# moja-col2.net
KiCad netlist of a schematic drawn in EAGLE
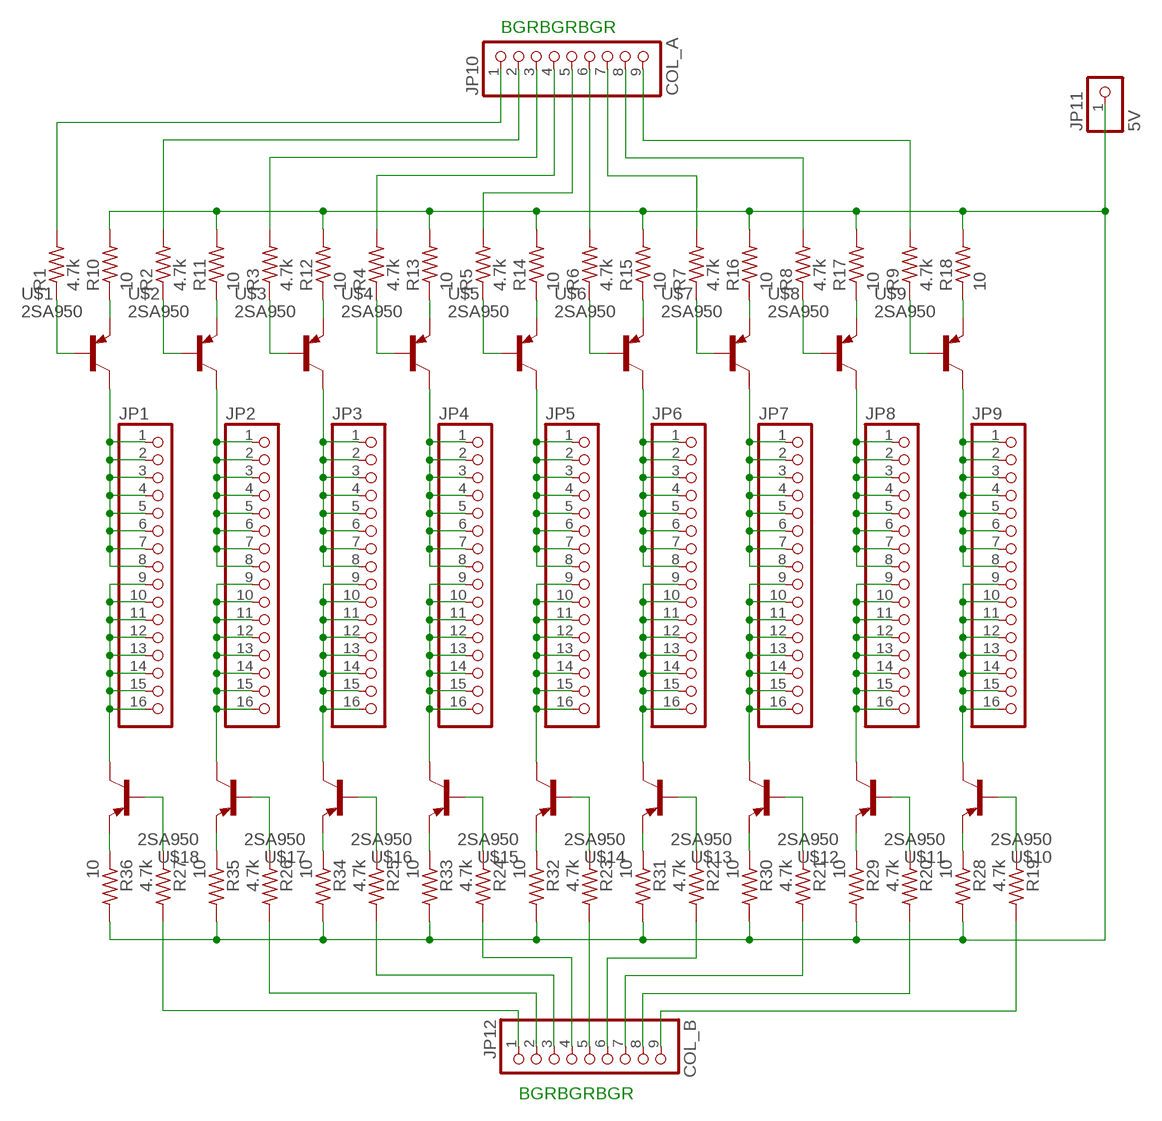
[diagram p0: schematic, sheet 1]

(export (version "E")
  (design (tool "Eeschema 10.0.6"))
  (components
    (comp (ref "JP1")
      (value "PINHD-1X16")
      (footprint "eagle-import:1X16")
      (libsource (lib "eagle-import") (part "PINHD-1X16"))
    )
    (comp (ref "JP2")
      (value "PINHD-1X16")
      (footprint "eagle-import:1X16")
      (libsource (lib "eagle-import") (part "PINHD-1X16"))
    )
    (comp (ref "JP3")
      (value "PINHD-1X16")
      (footprint "eagle-import:1X16")
      (libsource (lib "eagle-import") (part "PINHD-1X16"))
    )
    (comp (ref "JP4")
      (value "PINHD-1X16")
      (footprint "eagle-import:1X16")
      (libsource (lib "eagle-import") (part "PINHD-1X16"))
    )
    (comp (ref "JP5")
      (value "PINHD-1X16")
      (footprint "eagle-import:1X16")
      (libsource (lib "eagle-import") (part "PINHD-1X16"))
    )
    (comp (ref "JP6")
      (value "PINHD-1X16")
      (footprint "eagle-import:1X16")
      (libsource (lib "eagle-import") (part "PINHD-1X16"))
    )
    (comp (ref "JP7")
      (value "PINHD-1X16")
      (footprint "eagle-import:1X16")
      (libsource (lib "eagle-import") (part "PINHD-1X16"))
    )
    (comp (ref "JP8")
      (value "PINHD-1X16")
      (footprint "eagle-import:1X16")
      (libsource (lib "eagle-import") (part "PINHD-1X16"))
    )
    (comp (ref "JP9")
      (value "PINHD-1X16")
      (footprint "eagle-import:1X16")
      (libsource (lib "eagle-import") (part "PINHD-1X16"))
    )
    (comp (ref "JP10")
      (value "COL_A")
      (footprint "eagle-import:1X09")
      (libsource (lib "eagle-import") (part "PINHD-1X9"))
    )
    (comp (ref "JP11")
      (value "5V")
      (footprint "eagle-import:1X01")
      (libsource (lib "eagle-import") (part "PINHD-1X1"))
    )
    (comp (ref "JP12")
      (value "COL_B")
      (footprint "eagle-import:1X09")
      (libsource (lib "eagle-import") (part "PINHD-1X9"))
    )
    (comp (ref "R1")
      (value "4.7k")
      (footprint "eagle-import:0204V")
      (libsource (lib "eagle-import") (part "R-US_0204/2V"))
    )
    (comp (ref "R2")
      (value "4.7k")
      (footprint "eagle-import:0204V")
      (libsource (lib "eagle-import") (part "R-US_0204/2V"))
    )
    (comp (ref "R3")
      (value "4.7k")
      (footprint "eagle-import:0204V")
      (libsource (lib "eagle-import") (part "R-US_0204/2V"))
    )
    (comp (ref "R4")
      (value "4.7k")
      (footprint "eagle-import:0204V")
      (libsource (lib "eagle-import") (part "R-US_0204/2V"))
    )
    (comp (ref "R5")
      (value "4.7k")
      (footprint "eagle-import:0204V")
      (libsource (lib "eagle-import") (part "R-US_0204/2V"))
    )
    (comp (ref "R6")
      (value "4.7k")
      (footprint "eagle-import:0204V")
      (libsource (lib "eagle-import") (part "R-US_0204/2V"))
    )
    (comp (ref "R7")
      (value "4.7k")
      (footprint "eagle-import:0204V")
      (libsource (lib "eagle-import") (part "R-US_0204/2V"))
    )
    (comp (ref "R8")
      (value "4.7k")
      (footprint "eagle-import:0204V")
      (libsource (lib "eagle-import") (part "R-US_0204/2V"))
    )
    (comp (ref "R9")
      (value "4.7k")
      (footprint "eagle-import:0204V")
      (libsource (lib "eagle-import") (part "R-US_0204/2V"))
    )
    (comp (ref "R10")
      (value "10")
      (footprint "eagle-import:0204V")
      (libsource (lib "eagle-import") (part "R-US_0204/2V"))
    )
    (comp (ref "R11")
      (value "10")
      (footprint "eagle-import:0204V")
      (libsource (lib "eagle-import") (part "R-US_0204/2V"))
    )
    (comp (ref "R12")
      (value "10")
      (footprint "eagle-import:0204V")
      (libsource (lib "eagle-import") (part "R-US_0204/2V"))
    )
    (comp (ref "R13")
      (value "10")
      (footprint "eagle-import:0204V")
      (libsource (lib "eagle-import") (part "R-US_0204/2V"))
    )
    (comp (ref "R14")
      (value "10")
      (footprint "eagle-import:0204V")
      (libsource (lib "eagle-import") (part "R-US_0204/2V"))
    )
    (comp (ref "R15")
      (value "10")
      (footprint "eagle-import:0204V")
      (libsource (lib "eagle-import") (part "R-US_0204/2V"))
    )
    (comp (ref "R16")
      (value "10")
      (footprint "eagle-import:0204V")
      (libsource (lib "eagle-import") (part "R-US_0204/2V"))
    )
    (comp (ref "R17")
      (value "10")
      (footprint "eagle-import:0204V")
      (libsource (lib "eagle-import") (part "R-US_0204/2V"))
    )
    (comp (ref "R18")
      (value "10")
      (footprint "eagle-import:0204V")
      (libsource (lib "eagle-import") (part "R-US_0204/2V"))
    )
    (comp (ref "R19")
      (value "4.7k")
      (footprint "eagle-import:0204V")
      (libsource (lib "eagle-import") (part "R-US_0204/2V"))
    )
    (comp (ref "R20")
      (value "4.7k")
      (footprint "eagle-import:0204V")
      (libsource (lib "eagle-import") (part "R-US_0204/2V"))
    )
    (comp (ref "R21")
      (value "4.7k")
      (footprint "eagle-import:0204V")
      (libsource (lib "eagle-import") (part "R-US_0204/2V"))
    )
    (comp (ref "R22")
      (value "4.7k")
      (footprint "eagle-import:0204V")
      (libsource (lib "eagle-import") (part "R-US_0204/2V"))
    )
    (comp (ref "R23")
      (value "4.7k")
      (footprint "eagle-import:0204V")
      (libsource (lib "eagle-import") (part "R-US_0204/2V"))
    )
    (comp (ref "R24")
      (value "4.7k")
      (footprint "eagle-import:0204V")
      (libsource (lib "eagle-import") (part "R-US_0204/2V"))
    )
    (comp (ref "R25")
      (value "4.7k")
      (footprint "eagle-import:0204V")
      (libsource (lib "eagle-import") (part "R-US_0204/2V"))
    )
    (comp (ref "R26")
      (value "4.7k")
      (footprint "eagle-import:0204V")
      (libsource (lib "eagle-import") (part "R-US_0204/2V"))
    )
    (comp (ref "R27")
      (value "4.7k")
      (footprint "eagle-import:0204V")
      (libsource (lib "eagle-import") (part "R-US_0204/2V"))
    )
    (comp (ref "R28")
      (value "10")
      (footprint "eagle-import:0204V")
      (libsource (lib "eagle-import") (part "R-US_0204/2V"))
    )
    (comp (ref "R29")
      (value "10")
      (footprint "eagle-import:0204V")
      (libsource (lib "eagle-import") (part "R-US_0204/2V"))
    )
    (comp (ref "R30")
      (value "10")
      (footprint "eagle-import:0204V")
      (libsource (lib "eagle-import") (part "R-US_0204/2V"))
    )
    (comp (ref "R31")
      (value "10")
      (footprint "eagle-import:0204V")
      (libsource (lib "eagle-import") (part "R-US_0204/2V"))
    )
    (comp (ref "R32")
      (value "10")
      (footprint "eagle-import:0204V")
      (libsource (lib "eagle-import") (part "R-US_0204/2V"))
    )
    (comp (ref "R33")
      (value "10")
      (footprint "eagle-import:0204V")
      (libsource (lib "eagle-import") (part "R-US_0204/2V"))
    )
    (comp (ref "R34")
      (value "10")
      (footprint "eagle-import:0204V")
      (libsource (lib "eagle-import") (part "R-US_0204/2V"))
    )
    (comp (ref "R35")
      (value "10")
      (footprint "eagle-import:0204V")
      (libsource (lib "eagle-import") (part "R-US_0204/2V"))
    )
    (comp (ref "R36")
      (value "10")
      (footprint "eagle-import:0204V")
      (libsource (lib "eagle-import") (part "R-US_0204/2V"))
    )
    (comp (ref "U$1")
      (value "2SA950")
      (footprint "eagle-import:TO-92-AMMO")
      (libsource (lib "eagle-import") (part "2SA950"))
    )
    (comp (ref "U$2")
      (value "2SA950")
      (footprint "eagle-import:TO-92-AMMO")
      (libsource (lib "eagle-import") (part "2SA950"))
    )
    (comp (ref "U$3")
      (value "2SA950")
      (footprint "eagle-import:TO-92-AMMO")
      (libsource (lib "eagle-import") (part "2SA950"))
    )
    (comp (ref "U$4")
      (value "2SA950")
      (footprint "eagle-import:TO-92-AMMO")
      (libsource (lib "eagle-import") (part "2SA950"))
    )
    (comp (ref "U$5")
      (value "2SA950")
      (footprint "eagle-import:TO-92-AMMO")
      (libsource (lib "eagle-import") (part "2SA950"))
    )
    (comp (ref "U$6")
      (value "2SA950")
      (footprint "eagle-import:TO-92-AMMO")
      (libsource (lib "eagle-import") (part "2SA950"))
    )
    (comp (ref "U$7")
      (value "2SA950")
      (footprint "eagle-import:TO-92-AMMO")
      (libsource (lib "eagle-import") (part "2SA950"))
    )
    (comp (ref "U$8")
      (value "2SA950")
      (footprint "eagle-import:TO-92-AMMO")
      (libsource (lib "eagle-import") (part "2SA950"))
    )
    (comp (ref "U$9")
      (value "2SA950")
      (footprint "eagle-import:TO-92-AMMO")
      (libsource (lib "eagle-import") (part "2SA950"))
    )
    (comp (ref "U$10")
      (value "2SA950")
      (footprint "eagle-import:TO-92-AMMO")
      (libsource (lib "eagle-import") (part "2SA950"))
    )
    (comp (ref "U$11")
      (value "2SA950")
      (footprint "eagle-import:TO-92-AMMO")
      (libsource (lib "eagle-import") (part "2SA950"))
    )
    (comp (ref "U$12")
      (value "2SA950")
      (footprint "eagle-import:TO-92-AMMO")
      (libsource (lib "eagle-import") (part "2SA950"))
    )
    (comp (ref "U$13")
      (value "2SA950")
      (footprint "eagle-import:TO-92-AMMO")
      (libsource (lib "eagle-import") (part "2SA950"))
    )
    (comp (ref "U$14")
      (value "2SA950")
      (footprint "eagle-import:TO-92-AMMO")
      (libsource (lib "eagle-import") (part "2SA950"))
    )
    (comp (ref "U$15")
      (value "2SA950")
      (footprint "eagle-import:TO-92-AMMO")
      (libsource (lib "eagle-import") (part "2SA950"))
    )
    (comp (ref "U$16")
      (value "2SA950")
      (footprint "eagle-import:TO-92-AMMO")
      (libsource (lib "eagle-import") (part "2SA950"))
    )
    (comp (ref "U$17")
      (value "2SA950")
      (footprint "eagle-import:TO-92-AMMO")
      (libsource (lib "eagle-import") (part "2SA950"))
    )
    (comp (ref "U$18")
      (value "2SA950")
      (footprint "eagle-import:TO-92-AMMO")
      (libsource (lib "eagle-import") (part "2SA950"))
    )
  )
  (nets
    (net (code "1") (name "Net-(JP10-Pad1)") (class "Default")
      (node (ref "JP10") (pin "1") (pinfunction "1_1") (pintype "passive"))
      (node (ref "R1") (pin "2") (pinfunction "2_2") (pintype "passive"))
    )
    (net (code "2") (name "Net-(JP10-Pad2)") (class "Default")
      (node (ref "JP10") (pin "2") (pinfunction "2_2") (pintype "passive"))
      (node (ref "R2") (pin "2") (pinfunction "2_2") (pintype "passive"))
    )
    (net (code "3") (name "Net-(JP10-Pad3)") (class "Default")
      (node (ref "JP10") (pin "3") (pinfunction "3_3") (pintype "passive"))
      (node (ref "R3") (pin "2") (pinfunction "2_2") (pintype "passive"))
    )
    (net (code "4") (name "Net-(JP10-Pad4)") (class "Default")
      (node (ref "JP10") (pin "4") (pinfunction "4_4") (pintype "passive"))
      (node (ref "R4") (pin "2") (pinfunction "2_2") (pintype "passive"))
    )
    (net (code "5") (name "Net-(JP10-Pad5)") (class "Default")
      (node (ref "JP10") (pin "5") (pinfunction "5_5") (pintype "passive"))
      (node (ref "R5") (pin "2") (pinfunction "2_2") (pintype "passive"))
    )
    (net (code "6") (name "Net-(JP10-Pad6)") (class "Default")
      (node (ref "JP10") (pin "6") (pinfunction "6_6") (pintype "passive"))
      (node (ref "R6") (pin "2") (pinfunction "2_2") (pintype "passive"))
    )
    (net (code "7") (name "Net-(JP10-Pad7)") (class "Default")
      (node (ref "JP10") (pin "7") (pinfunction "7_7") (pintype "passive"))
      (node (ref "R7") (pin "2") (pinfunction "2_2") (pintype "passive"))
    )
    (net (code "8") (name "Net-(JP10-Pad8)") (class "Default")
      (node (ref "JP10") (pin "8") (pinfunction "8_8") (pintype "passive"))
      (node (ref "R8") (pin "2") (pinfunction "2_2") (pintype "passive"))
    )
    (net (code "9") (name "Net-(JP10-Pad9)") (class "Default")
      (node (ref "JP10") (pin "9") (pinfunction "9_9") (pintype "passive"))
      (node (ref "R9") (pin "2") (pinfunction "2_2") (pintype "passive"))
    )
    (net (code "10") (name "Net-(JP11-Pad1)") (class "Default")
      (node (ref "JP11") (pin "1") (pinfunction "1_1") (pintype "passive"))
      (node (ref "R10") (pin "2") (pinfunction "2_2") (pintype "passive"))
      (node (ref "R11") (pin "2") (pinfunction "2_2") (pintype "passive"))
      (node (ref "R12") (pin "2") (pinfunction "2_2") (pintype "passive"))
      (node (ref "R13") (pin "2") (pinfunction "2_2") (pintype "passive"))
      (node (ref "R14") (pin "2") (pinfunction "2_2") (pintype "passive"))
      (node (ref "R15") (pin "2") (pinfunction "2_2") (pintype "passive"))
      (node (ref "R16") (pin "2") (pinfunction "2_2") (pintype "passive"))
      (node (ref "R17") (pin "2") (pinfunction "2_2") (pintype "passive"))
      (node (ref "R18") (pin "2") (pinfunction "2_2") (pintype "passive"))
      (node (ref "R28") (pin "2") (pinfunction "2_2") (pintype "passive"))
      (node (ref "R29") (pin "2") (pinfunction "2_2") (pintype "passive"))
      (node (ref "R30") (pin "2") (pinfunction "2_2") (pintype "passive"))
      (node (ref "R31") (pin "2") (pinfunction "2_2") (pintype "passive"))
      (node (ref "R32") (pin "2") (pinfunction "2_2") (pintype "passive"))
      (node (ref "R33") (pin "2") (pinfunction "2_2") (pintype "passive"))
      (node (ref "R34") (pin "2") (pinfunction "2_2") (pintype "passive"))
      (node (ref "R35") (pin "2") (pinfunction "2_2") (pintype "passive"))
      (node (ref "R36") (pin "2") (pinfunction "2_2") (pintype "passive"))
    )
    (net (code "11") (name "Net-(JP12-Pad1)") (class "Default")
      (node (ref "JP12") (pin "1") (pinfunction "1_1") (pintype "passive"))
      (node (ref "R27") (pin "2") (pinfunction "2_2") (pintype "passive"))
    )
    (net (code "12") (name "Net-(JP12-Pad2)") (class "Default")
      (node (ref "JP12") (pin "2") (pinfunction "2_2") (pintype "passive"))
      (node (ref "R26") (pin "2") (pinfunction "2_2") (pintype "passive"))
    )
    (net (code "13") (name "Net-(JP12-Pad3)") (class "Default")
      (node (ref "JP12") (pin "3") (pinfunction "3_3") (pintype "passive"))
      (node (ref "R25") (pin "2") (pinfunction "2_2") (pintype "passive"))
    )
    (net (code "14") (name "Net-(JP12-Pad4)") (class "Default")
      (node (ref "JP12") (pin "4") (pinfunction "4_4") (pintype "passive"))
      (node (ref "R24") (pin "2") (pinfunction "2_2") (pintype "passive"))
    )
    (net (code "15") (name "Net-(JP12-Pad5)") (class "Default")
      (node (ref "JP12") (pin "5") (pinfunction "5_5") (pintype "passive"))
      (node (ref "R23") (pin "2") (pinfunction "2_2") (pintype "passive"))
    )
    (net (code "16") (name "Net-(JP12-Pad6)") (class "Default")
      (node (ref "JP12") (pin "6") (pinfunction "6_6") (pintype "passive"))
      (node (ref "R22") (pin "2") (pinfunction "2_2") (pintype "passive"))
    )
    (net (code "17") (name "Net-(JP12-Pad7)") (class "Default")
      (node (ref "JP12") (pin "7") (pinfunction "7_7") (pintype "passive"))
      (node (ref "R21") (pin "2") (pinfunction "2_2") (pintype "passive"))
    )
    (net (code "18") (name "Net-(JP12-Pad8)") (class "Default")
      (node (ref "JP12") (pin "8") (pinfunction "8_8") (pintype "passive"))
      (node (ref "R20") (pin "2") (pinfunction "2_2") (pintype "passive"))
    )
    (net (code "19") (name "Net-(JP12-Pad9)") (class "Default")
      (node (ref "JP12") (pin "9") (pinfunction "9_9") (pintype "passive"))
      (node (ref "R19") (pin "2") (pinfunction "2_2") (pintype "passive"))
    )
    (net (code "20") (name "Net-(U$1-B)") (class "Default")
      (node (ref "R1") (pin "1") (pinfunction "1_1") (pintype "passive"))
      (node (ref "U$1") (pin "3") (pinfunction "B_3") (pintype "passive"))
    )
    (net (code "21") (name "Net-(U$1-C)") (class "Default")
      (node (ref "JP1") (pin "1") (pinfunction "1_1") (pintype "passive"))
      (node (ref "JP1") (pin "2") (pinfunction "2_2") (pintype "passive"))
      (node (ref "JP1") (pin "3") (pinfunction "3_3") (pintype "passive"))
      (node (ref "JP1") (pin "4") (pinfunction "4_4") (pintype "passive"))
      (node (ref "JP1") (pin "5") (pinfunction "5_5") (pintype "passive"))
      (node (ref "JP1") (pin "6") (pinfunction "6_6") (pintype "passive"))
      (node (ref "JP1") (pin "7") (pinfunction "7_7") (pintype "passive"))
      (node (ref "JP1") (pin "8") (pinfunction "8_8") (pintype "passive"))
      (node (ref "U$1") (pin "2") (pinfunction "C_2") (pintype "passive"))
    )
    (net (code "22") (name "Net-(U$1-E)") (class "Default")
      (node (ref "R10") (pin "1") (pinfunction "1_1") (pintype "passive"))
      (node (ref "U$1") (pin "1") (pinfunction "E_1") (pintype "passive"))
    )
    (net (code "23") (name "Net-(U$2-B)") (class "Default")
      (node (ref "R2") (pin "1") (pinfunction "1_1") (pintype "passive"))
      (node (ref "U$2") (pin "3") (pinfunction "B_3") (pintype "passive"))
    )
    (net (code "24") (name "Net-(U$2-C)") (class "Default")
      (node (ref "JP2") (pin "1") (pinfunction "1_1") (pintype "passive"))
      (node (ref "JP2") (pin "2") (pinfunction "2_2") (pintype "passive"))
      (node (ref "JP2") (pin "3") (pinfunction "3_3") (pintype "passive"))
      (node (ref "JP2") (pin "4") (pinfunction "4_4") (pintype "passive"))
      (node (ref "JP2") (pin "5") (pinfunction "5_5") (pintype "passive"))
      (node (ref "JP2") (pin "6") (pinfunction "6_6") (pintype "passive"))
      (node (ref "JP2") (pin "7") (pinfunction "7_7") (pintype "passive"))
      (node (ref "JP2") (pin "8") (pinfunction "8_8") (pintype "passive"))
      (node (ref "U$2") (pin "2") (pinfunction "C_2") (pintype "passive"))
    )
    (net (code "25") (name "Net-(U$2-E)") (class "Default")
      (node (ref "R11") (pin "1") (pinfunction "1_1") (pintype "passive"))
      (node (ref "U$2") (pin "1") (pinfunction "E_1") (pintype "passive"))
    )
    (net (code "26") (name "Net-(U$3-B)") (class "Default")
      (node (ref "R3") (pin "1") (pinfunction "1_1") (pintype "passive"))
      (node (ref "U$3") (pin "3") (pinfunction "B_3") (pintype "passive"))
    )
    (net (code "27") (name "Net-(U$3-C)") (class "Default")
      (node (ref "JP3") (pin "1") (pinfunction "1_1") (pintype "passive"))
      (node (ref "JP3") (pin "2") (pinfunction "2_2") (pintype "passive"))
      (node (ref "JP3") (pin "3") (pinfunction "3_3") (pintype "passive"))
      (node (ref "JP3") (pin "4") (pinfunction "4_4") (pintype "passive"))
      (node (ref "JP3") (pin "5") (pinfunction "5_5") (pintype "passive"))
      (node (ref "JP3") (pin "6") (pinfunction "6_6") (pintype "passive"))
      (node (ref "JP3") (pin "7") (pinfunction "7_7") (pintype "passive"))
      (node (ref "JP3") (pin "8") (pinfunction "8_8") (pintype "passive"))
      (node (ref "U$3") (pin "2") (pinfunction "C_2") (pintype "passive"))
    )
    (net (code "28") (name "Net-(U$3-E)") (class "Default")
      (node (ref "R12") (pin "1") (pinfunction "1_1") (pintype "passive"))
      (node (ref "U$3") (pin "1") (pinfunction "E_1") (pintype "passive"))
    )
    (net (code "29") (name "Net-(U$4-B)") (class "Default")
      (node (ref "R4") (pin "1") (pinfunction "1_1") (pintype "passive"))
      (node (ref "U$4") (pin "3") (pinfunction "B_3") (pintype "passive"))
    )
    (net (code "30") (name "Net-(U$4-C)") (class "Default")
      (node (ref "JP4") (pin "1") (pinfunction "1_1") (pintype "passive"))
      (node (ref "JP4") (pin "2") (pinfunction "2_2") (pintype "passive"))
      (node (ref "JP4") (pin "3") (pinfunction "3_3") (pintype "passive"))
      (node (ref "JP4") (pin "4") (pinfunction "4_4") (pintype "passive"))
      (node (ref "JP4") (pin "5") (pinfunction "5_5") (pintype "passive"))
      (node (ref "JP4") (pin "6") (pinfunction "6_6") (pintype "passive"))
      (node (ref "JP4") (pin "7") (pinfunction "7_7") (pintype "passive"))
      (node (ref "JP4") (pin "8") (pinfunction "8_8") (pintype "passive"))
      (node (ref "U$4") (pin "2") (pinfunction "C_2") (pintype "passive"))
    )
    (net (code "31") (name "Net-(U$4-E)") (class "Default")
      (node (ref "R13") (pin "1") (pinfunction "1_1") (pintype "passive"))
      (node (ref "U$4") (pin "1") (pinfunction "E_1") (pintype "passive"))
    )
    (net (code "32") (name "Net-(U$5-B)") (class "Default")
      (node (ref "R5") (pin "1") (pinfunction "1_1") (pintype "passive"))
      (node (ref "U$5") (pin "3") (pinfunction "B_3") (pintype "passive"))
    )
    (net (code "33") (name "Net-(U$5-C)") (class "Default")
      (node (ref "JP5") (pin "1") (pinfunction "1_1") (pintype "passive"))
      (node (ref "JP5") (pin "2") (pinfunction "2_2") (pintype "passive"))
      (node (ref "JP5") (pin "3") (pinfunction "3_3") (pintype "passive"))
      (node (ref "JP5") (pin "4") (pinfunction "4_4") (pintype "passive"))
      (node (ref "JP5") (pin "5") (pinfunction "5_5") (pintype "passive"))
      (node (ref "JP5") (pin "6") (pinfunction "6_6") (pintype "passive"))
      (node (ref "JP5") (pin "7") (pinfunction "7_7") (pintype "passive"))
      (node (ref "JP5") (pin "8") (pinfunction "8_8") (pintype "passive"))
      (node (ref "U$5") (pin "2") (pinfunction "C_2") (pintype "passive"))
    )
    (net (code "34") (name "Net-(U$5-E)") (class "Default")
      (node (ref "R14") (pin "1") (pinfunction "1_1") (pintype "passive"))
      (node (ref "U$5") (pin "1") (pinfunction "E_1") (pintype "passive"))
    )
    (net (code "35") (name "Net-(U$6-B)") (class "Default")
      (node (ref "R6") (pin "1") (pinfunction "1_1") (pintype "passive"))
      (node (ref "U$6") (pin "3") (pinfunction "B_3") (pintype "passive"))
    )
    (net (code "36") (name "Net-(U$6-C)") (class "Default")
      (node (ref "JP6") (pin "1") (pinfunction "1_1") (pintype "passive"))
      (node (ref "JP6") (pin "2") (pinfunction "2_2") (pintype "passive"))
      (node (ref "JP6") (pin "3") (pinfunction "3_3") (pintype "passive"))
      (node (ref "JP6") (pin "4") (pinfunction "4_4") (pintype "passive"))
      (node (ref "JP6") (pin "5") (pinfunction "5_5") (pintype "passive"))
      (node (ref "JP6") (pin "6") (pinfunction "6_6") (pintype "passive"))
      (node (ref "JP6") (pin "7") (pinfunction "7_7") (pintype "passive"))
      (node (ref "JP6") (pin "8") (pinfunction "8_8") (pintype "passive"))
      (node (ref "U$6") (pin "2") (pinfunction "C_2") (pintype "passive"))
    )
    (net (code "37") (name "Net-(U$6-E)") (class "Default")
      (node (ref "R15") (pin "1") (pinfunction "1_1") (pintype "passive"))
      (node (ref "U$6") (pin "1") (pinfunction "E_1") (pintype "passive"))
    )
    (net (code "38") (name "Net-(U$7-B)") (class "Default")
      (node (ref "R7") (pin "1") (pinfunction "1_1") (pintype "passive"))
      (node (ref "U$7") (pin "3") (pinfunction "B_3") (pintype "passive"))
    )
    (net (code "39") (name "Net-(U$7-C)") (class "Default")
      (node (ref "JP7") (pin "1") (pinfunction "1_1") (pintype "passive"))
      (node (ref "JP7") (pin "2") (pinfunction "2_2") (pintype "passive"))
      (node (ref "JP7") (pin "3") (pinfunction "3_3") (pintype "passive"))
      (node (ref "JP7") (pin "4") (pinfunction "4_4") (pintype "passive"))
      (node (ref "JP7") (pin "5") (pinfunction "5_5") (pintype "passive"))
      (node (ref "JP7") (pin "6") (pinfunction "6_6") (pintype "passive"))
      (node (ref "JP7") (pin "7") (pinfunction "7_7") (pintype "passive"))
      (node (ref "JP7") (pin "8") (pinfunction "8_8") (pintype "passive"))
      (node (ref "U$7") (pin "2") (pinfunction "C_2") (pintype "passive"))
    )
    (net (code "40") (name "Net-(U$7-E)") (class "Default")
      (node (ref "R16") (pin "1") (pinfunction "1_1") (pintype "passive"))
      (node (ref "U$7") (pin "1") (pinfunction "E_1") (pintype "passive"))
    )
    (net (code "41") (name "Net-(U$8-B)") (class "Default")
      (node (ref "R8") (pin "1") (pinfunction "1_1") (pintype "passive"))
      (node (ref "U$8") (pin "3") (pinfunction "B_3") (pintype "passive"))
    )
    (net (code "42") (name "Net-(U$8-C)") (class "Default")
      (node (ref "JP8") (pin "1") (pinfunction "1_1") (pintype "passive"))
      (node (ref "JP8") (pin "2") (pinfunction "2_2") (pintype "passive"))
      (node (ref "JP8") (pin "3") (pinfunction "3_3") (pintype "passive"))
      (node (ref "JP8") (pin "4") (pinfunction "4_4") (pintype "passive"))
      (node (ref "JP8") (pin "5") (pinfunction "5_5") (pintype "passive"))
      (node (ref "JP8") (pin "6") (pinfunction "6_6") (pintype "passive"))
      (node (ref "JP8") (pin "7") (pinfunction "7_7") (pintype "passive"))
      (node (ref "JP8") (pin "8") (pinfunction "8_8") (pintype "passive"))
      (node (ref "U$8") (pin "2") (pinfunction "C_2") (pintype "passive"))
    )
    (net (code "43") (name "Net-(U$8-E)") (class "Default")
      (node (ref "R17") (pin "1") (pinfunction "1_1") (pintype "passive"))
      (node (ref "U$8") (pin "1") (pinfunction "E_1") (pintype "passive"))
    )
    (net (code "44") (name "Net-(U$9-B)") (class "Default")
      (node (ref "R9") (pin "1") (pinfunction "1_1") (pintype "passive"))
      (node (ref "U$9") (pin "3") (pinfunction "B_3") (pintype "passive"))
    )
    (net (code "45") (name "Net-(U$9-C)") (class "Default")
      (node (ref "JP9") (pin "1") (pinfunction "1_1") (pintype "passive"))
      (node (ref "JP9") (pin "2") (pinfunction "2_2") (pintype "passive"))
      (node (ref "JP9") (pin "3") (pinfunction "3_3") (pintype "passive"))
      (node (ref "JP9") (pin "4") (pinfunction "4_4") (pintype "passive"))
      (node (ref "JP9") (pin "5") (pinfunction "5_5") (pintype "passive"))
      (node (ref "JP9") (pin "6") (pinfunction "6_6") (pintype "passive"))
      (node (ref "JP9") (pin "7") (pinfunction "7_7") (pintype "passive"))
      (node (ref "JP9") (pin "8") (pinfunction "8_8") (pintype "passive"))
      (node (ref "U$9") (pin "2") (pinfunction "C_2") (pintype "passive"))
    )
    (net (code "46") (name "Net-(U$9-E)") (class "Default")
      (node (ref "R18") (pin "1") (pinfunction "1_1") (pintype "passive"))
      (node (ref "U$9") (pin "1") (pinfunction "E_1") (pintype "passive"))
    )
    (net (code "47") (name "Net-(U$10-B)") (class "Default")
      (node (ref "R19") (pin "1") (pinfunction "1_1") (pintype "passive"))
      (node (ref "U$10") (pin "3") (pinfunction "B_3") (pintype "passive"))
    )
    (net (code "48") (name "Net-(U$10-C)") (class "Default")
      (node (ref "JP9") (pin "10") (pinfunction "10_10") (pintype "passive"))
      (node (ref "JP9") (pin "11") (pinfunction "11_11") (pintype "passive"))
      (node (ref "JP9") (pin "12") (pinfunction "12_12") (pintype "passive"))
      (node (ref "JP9") (pin "13") (pinfunction "13_13") (pintype "passive"))
      (node (ref "JP9") (pin "14") (pinfunction "14_14") (pintype "passive"))
      (node (ref "JP9") (pin "15") (pinfunction "15_15") (pintype "passive"))
      (node (ref "JP9") (pin "16") (pinfunction "16_16") (pintype "passive"))
      (node (ref "JP9") (pin "9") (pinfunction "9_9") (pintype "passive"))
      (node (ref "U$10") (pin "2") (pinfunction "C_2") (pintype "passive"))
    )
    (net (code "49") (name "Net-(U$10-E)") (class "Default")
      (node (ref "R28") (pin "1") (pinfunction "1_1") (pintype "passive"))
      (node (ref "U$10") (pin "1") (pinfunction "E_1") (pintype "passive"))
    )
    (net (code "50") (name "Net-(U$11-B)") (class "Default")
      (node (ref "R20") (pin "1") (pinfunction "1_1") (pintype "passive"))
      (node (ref "U$11") (pin "3") (pinfunction "B_3") (pintype "passive"))
    )
    (net (code "51") (name "Net-(U$11-C)") (class "Default")
      (node (ref "JP8") (pin "10") (pinfunction "10_10") (pintype "passive"))
      (node (ref "JP8") (pin "11") (pinfunction "11_11") (pintype "passive"))
      (node (ref "JP8") (pin "12") (pinfunction "12_12") (pintype "passive"))
      (node (ref "JP8") (pin "13") (pinfunction "13_13") (pintype "passive"))
      (node (ref "JP8") (pin "14") (pinfunction "14_14") (pintype "passive"))
      (node (ref "JP8") (pin "15") (pinfunction "15_15") (pintype "passive"))
      (node (ref "JP8") (pin "16") (pinfunction "16_16") (pintype "passive"))
      (node (ref "JP8") (pin "9") (pinfunction "9_9") (pintype "passive"))
      (node (ref "U$11") (pin "2") (pinfunction "C_2") (pintype "passive"))
    )
    (net (code "52") (name "Net-(U$11-E)") (class "Default")
      (node (ref "R29") (pin "1") (pinfunction "1_1") (pintype "passive"))
      (node (ref "U$11") (pin "1") (pinfunction "E_1") (pintype "passive"))
    )
    (net (code "53") (name "Net-(U$12-B)") (class "Default")
      (node (ref "R21") (pin "1") (pinfunction "1_1") (pintype "passive"))
      (node (ref "U$12") (pin "3") (pinfunction "B_3") (pintype "passive"))
    )
    (net (code "54") (name "Net-(U$12-C)") (class "Default")
      (node (ref "JP7") (pin "10") (pinfunction "10_10") (pintype "passive"))
      (node (ref "JP7") (pin "11") (pinfunction "11_11") (pintype "passive"))
      (node (ref "JP7") (pin "12") (pinfunction "12_12") (pintype "passive"))
      (node (ref "JP7") (pin "13") (pinfunction "13_13") (pintype "passive"))
      (node (ref "JP7") (pin "14") (pinfunction "14_14") (pintype "passive"))
      (node (ref "JP7") (pin "15") (pinfunction "15_15") (pintype "passive"))
      (node (ref "JP7") (pin "16") (pinfunction "16_16") (pintype "passive"))
      (node (ref "JP7") (pin "9") (pinfunction "9_9") (pintype "passive"))
      (node (ref "U$12") (pin "2") (pinfunction "C_2") (pintype "passive"))
    )
    (net (code "55") (name "Net-(U$12-E)") (class "Default")
      (node (ref "R30") (pin "1") (pinfunction "1_1") (pintype "passive"))
      (node (ref "U$12") (pin "1") (pinfunction "E_1") (pintype "passive"))
    )
    (net (code "56") (name "Net-(U$13-B)") (class "Default")
      (node (ref "R22") (pin "1") (pinfunction "1_1") (pintype "passive"))
      (node (ref "U$13") (pin "3") (pinfunction "B_3") (pintype "passive"))
    )
    (net (code "57") (name "Net-(U$13-C)") (class "Default")
      (node (ref "JP6") (pin "10") (pinfunction "10_10") (pintype "passive"))
      (node (ref "JP6") (pin "11") (pinfunction "11_11") (pintype "passive"))
      (node (ref "JP6") (pin "12") (pinfunction "12_12") (pintype "passive"))
      (node (ref "JP6") (pin "13") (pinfunction "13_13") (pintype "passive"))
      (node (ref "JP6") (pin "14") (pinfunction "14_14") (pintype "passive"))
      (node (ref "JP6") (pin "15") (pinfunction "15_15") (pintype "passive"))
      (node (ref "JP6") (pin "16") (pinfunction "16_16") (pintype "passive"))
      (node (ref "JP6") (pin "9") (pinfunction "9_9") (pintype "passive"))
      (node (ref "U$13") (pin "2") (pinfunction "C_2") (pintype "passive"))
    )
    (net (code "58") (name "Net-(U$13-E)") (class "Default")
      (node (ref "R31") (pin "1") (pinfunction "1_1") (pintype "passive"))
      (node (ref "U$13") (pin "1") (pinfunction "E_1") (pintype "passive"))
    )
    (net (code "59") (name "Net-(U$14-B)") (class "Default")
      (node (ref "R23") (pin "1") (pinfunction "1_1") (pintype "passive"))
      (node (ref "U$14") (pin "3") (pinfunction "B_3") (pintype "passive"))
    )
    (net (code "60") (name "Net-(U$14-C)") (class "Default")
      (node (ref "JP5") (pin "10") (pinfunction "10_10") (pintype "passive"))
      (node (ref "JP5") (pin "11") (pinfunction "11_11") (pintype "passive"))
      (node (ref "JP5") (pin "12") (pinfunction "12_12") (pintype "passive"))
      (node (ref "JP5") (pin "13") (pinfunction "13_13") (pintype "passive"))
      (node (ref "JP5") (pin "14") (pinfunction "14_14") (pintype "passive"))
      (node (ref "JP5") (pin "15") (pinfunction "15_15") (pintype "passive"))
      (node (ref "JP5") (pin "16") (pinfunction "16_16") (pintype "passive"))
      (node (ref "JP5") (pin "9") (pinfunction "9_9") (pintype "passive"))
      (node (ref "U$14") (pin "2") (pinfunction "C_2") (pintype "passive"))
    )
    (net (code "61") (name "Net-(U$14-E)") (class "Default")
      (node (ref "R32") (pin "1") (pinfunction "1_1") (pintype "passive"))
      (node (ref "U$14") (pin "1") (pinfunction "E_1") (pintype "passive"))
    )
    (net (code "62") (name "Net-(U$15-B)") (class "Default")
      (node (ref "R24") (pin "1") (pinfunction "1_1") (pintype "passive"))
      (node (ref "U$15") (pin "3") (pinfunction "B_3") (pintype "passive"))
    )
    (net (code "63") (name "Net-(U$15-C)") (class "Default")
      (node (ref "JP4") (pin "10") (pinfunction "10_10") (pintype "passive"))
      (node (ref "JP4") (pin "11") (pinfunction "11_11") (pintype "passive"))
      (node (ref "JP4") (pin "12") (pinfunction "12_12") (pintype "passive"))
      (node (ref "JP4") (pin "13") (pinfunction "13_13") (pintype "passive"))
      (node (ref "JP4") (pin "14") (pinfunction "14_14") (pintype "passive"))
      (node (ref "JP4") (pin "15") (pinfunction "15_15") (pintype "passive"))
      (node (ref "JP4") (pin "16") (pinfunction "16_16") (pintype "passive"))
      (node (ref "JP4") (pin "9") (pinfunction "9_9") (pintype "passive"))
      (node (ref "U$15") (pin "2") (pinfunction "C_2") (pintype "passive"))
    )
    (net (code "64") (name "Net-(U$15-E)") (class "Default")
      (node (ref "R33") (pin "1") (pinfunction "1_1") (pintype "passive"))
      (node (ref "U$15") (pin "1") (pinfunction "E_1") (pintype "passive"))
    )
    (net (code "65") (name "Net-(U$16-B)") (class "Default")
      (node (ref "R25") (pin "1") (pinfunction "1_1") (pintype "passive"))
      (node (ref "U$16") (pin "3") (pinfunction "B_3") (pintype "passive"))
    )
    (net (code "66") (name "Net-(U$16-C)") (class "Default")
      (node (ref "JP3") (pin "10") (pinfunction "10_10") (pintype "passive"))
      (node (ref "JP3") (pin "11") (pinfunction "11_11") (pintype "passive"))
      (node (ref "JP3") (pin "12") (pinfunction "12_12") (pintype "passive"))
      (node (ref "JP3") (pin "13") (pinfunction "13_13") (pintype "passive"))
      (node (ref "JP3") (pin "14") (pinfunction "14_14") (pintype "passive"))
      (node (ref "JP3") (pin "15") (pinfunction "15_15") (pintype "passive"))
      (node (ref "JP3") (pin "16") (pinfunction "16_16") (pintype "passive"))
      (node (ref "JP3") (pin "9") (pinfunction "9_9") (pintype "passive"))
      (node (ref "U$16") (pin "2") (pinfunction "C_2") (pintype "passive"))
    )
    (net (code "67") (name "Net-(U$16-E)") (class "Default")
      (node (ref "R34") (pin "1") (pinfunction "1_1") (pintype "passive"))
      (node (ref "U$16") (pin "1") (pinfunction "E_1") (pintype "passive"))
    )
    (net (code "68") (name "Net-(U$17-B)") (class "Default")
      (node (ref "R26") (pin "1") (pinfunction "1_1") (pintype "passive"))
      (node (ref "U$17") (pin "3") (pinfunction "B_3") (pintype "passive"))
    )
    (net (code "69") (name "Net-(U$17-C)") (class "Default")
      (node (ref "JP2") (pin "10") (pinfunction "10_10") (pintype "passive"))
      (node (ref "JP2") (pin "11") (pinfunction "11_11") (pintype "passive"))
      (node (ref "JP2") (pin "12") (pinfunction "12_12") (pintype "passive"))
      (node (ref "JP2") (pin "13") (pinfunction "13_13") (pintype "passive"))
      (node (ref "JP2") (pin "14") (pinfunction "14_14") (pintype "passive"))
      (node (ref "JP2") (pin "15") (pinfunction "15_15") (pintype "passive"))
      (node (ref "JP2") (pin "16") (pinfunction "16_16") (pintype "passive"))
      (node (ref "JP2") (pin "9") (pinfunction "9_9") (pintype "passive"))
      (node (ref "U$17") (pin "2") (pinfunction "C_2") (pintype "passive"))
    )
    (net (code "70") (name "Net-(U$17-E)") (class "Default")
      (node (ref "R35") (pin "1") (pinfunction "1_1") (pintype "passive"))
      (node (ref "U$17") (pin "1") (pinfunction "E_1") (pintype "passive"))
    )
    (net (code "71") (name "Net-(U$18-B)") (class "Default")
      (node (ref "R27") (pin "1") (pinfunction "1_1") (pintype "passive"))
      (node (ref "U$18") (pin "3") (pinfunction "B_3") (pintype "passive"))
    )
    (net (code "72") (name "Net-(U$18-C)") (class "Default")
      (node (ref "JP1") (pin "10") (pinfunction "10_10") (pintype "passive"))
      (node (ref "JP1") (pin "11") (pinfunction "11_11") (pintype "passive"))
      (node (ref "JP1") (pin "12") (pinfunction "12_12") (pintype "passive"))
      (node (ref "JP1") (pin "13") (pinfunction "13_13") (pintype "passive"))
      (node (ref "JP1") (pin "14") (pinfunction "14_14") (pintype "passive"))
      (node (ref "JP1") (pin "15") (pinfunction "15_15") (pintype "passive"))
      (node (ref "JP1") (pin "16") (pinfunction "16_16") (pintype "passive"))
      (node (ref "JP1") (pin "9") (pinfunction "9_9") (pintype "passive"))
      (node (ref "U$18") (pin "2") (pinfunction "C_2") (pintype "passive"))
    )
    (net (code "73") (name "Net-(U$18-E)") (class "Default")
      (node (ref "R36") (pin "1") (pinfunction "1_1") (pintype "passive"))
      (node (ref "U$18") (pin "1") (pinfunction "E_1") (pintype "passive"))
    )
  )
)
